# 5_SDRAM.net
KiCad netlist of a schematic drawn in Altium Designer
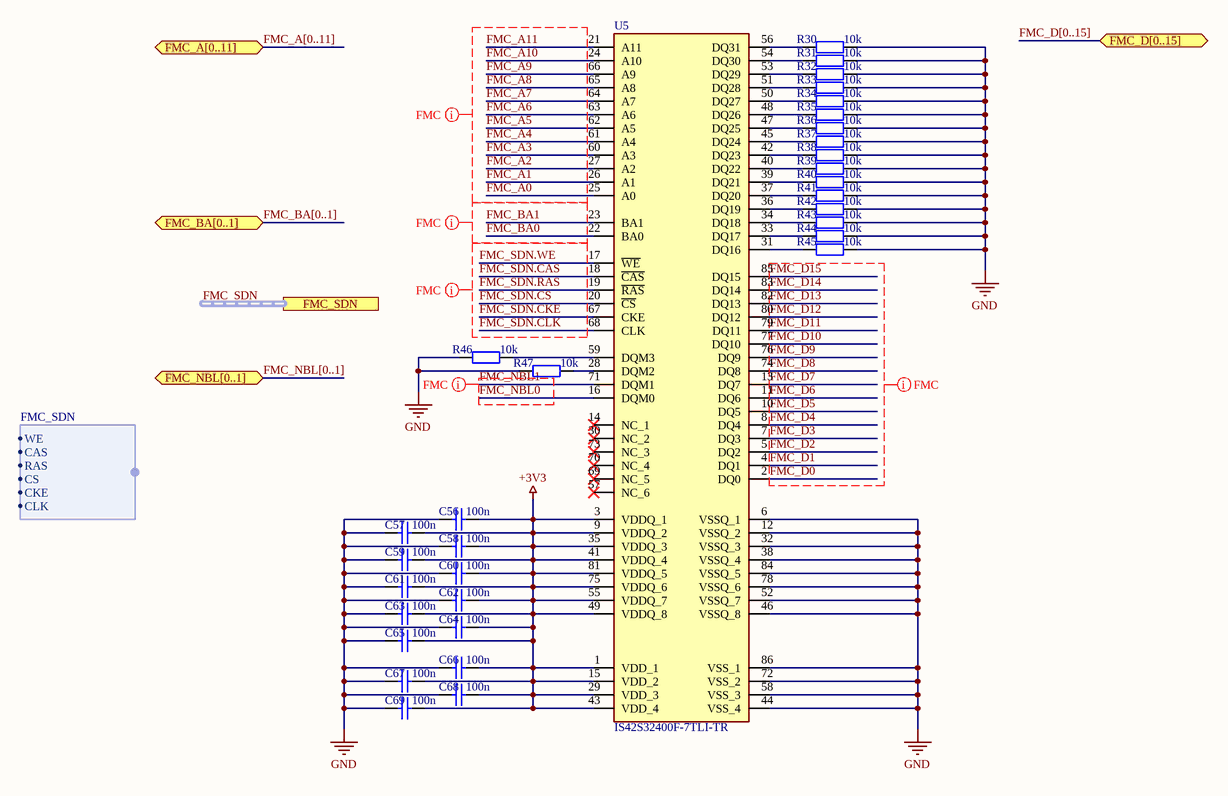
[diagram p0: [5] SDRAM.SchDoc]

(export (version "E")
  (design (tool "Eeschema 10.0.6"))
  (components
    (comp (ref "C56")
      (value "100n")
      (footprint "STguitar:Capacitor 0603")
      (description "Multilayer Ceramic Capacitors MLCC - SMD/SMT 0603 16VDC 0.1uF 10% X7R")
      (fields
        (field (name "MANUFACTURER PART NUMBER") "EMK107B7104KA-T")
        (field (name "MANUFACTURER") "Taiyo Yuden")
      )
      (libsource (lib "STguitar") (part "Capacitor 100n 10% 0603 EMK107B7104KA-T"))
    )
    (comp (ref "C57")
      (value "100n")
      (footprint "STguitar:Capacitor 0603")
      (description "Multilayer Ceramic Capacitors MLCC - SMD/SMT 0603 16VDC 0.1uF 10% X7R")
      (fields
        (field (name "MANUFACTURER PART NUMBER") "EMK107B7104KA-T")
        (field (name "MANUFACTURER") "Taiyo Yuden")
      )
      (libsource (lib "STguitar") (part "Capacitor 100n 10% 0603 EMK107B7104KA-T"))
    )
    (comp (ref "C58")
      (value "100n")
      (footprint "STguitar:Capacitor 0603")
      (description "Multilayer Ceramic Capacitors MLCC - SMD/SMT 0603 16VDC 0.1uF 10% X7R")
      (fields
        (field (name "MANUFACTURER PART NUMBER") "EMK107B7104KA-T")
        (field (name "MANUFACTURER") "Taiyo Yuden")
      )
      (libsource (lib "STguitar") (part "Capacitor 100n 10% 0603 EMK107B7104KA-T"))
    )
    (comp (ref "C59")
      (value "100n")
      (footprint "STguitar:Capacitor 0603")
      (description "Multilayer Ceramic Capacitors MLCC - SMD/SMT 0603 16VDC 0.1uF 10% X7R")
      (fields
        (field (name "MANUFACTURER PART NUMBER") "EMK107B7104KA-T")
        (field (name "MANUFACTURER") "Taiyo Yuden")
      )
      (libsource (lib "STguitar") (part "Capacitor 100n 10% 0603 EMK107B7104KA-T"))
    )
    (comp (ref "C60")
      (value "100n")
      (footprint "STguitar:Capacitor 0603")
      (description "Multilayer Ceramic Capacitors MLCC - SMD/SMT 0603 16VDC 0.1uF 10% X7R")
      (fields
        (field (name "MANUFACTURER PART NUMBER") "EMK107B7104KA-T")
        (field (name "MANUFACTURER") "Taiyo Yuden")
      )
      (libsource (lib "STguitar") (part "Capacitor 100n 10% 0603 EMK107B7104KA-T"))
    )
    (comp (ref "C61")
      (value "100n")
      (footprint "STguitar:Capacitor 0603")
      (description "Multilayer Ceramic Capacitors MLCC - SMD/SMT 0603 16VDC 0.1uF 10% X7R")
      (fields
        (field (name "MANUFACTURER PART NUMBER") "EMK107B7104KA-T")
        (field (name "MANUFACTURER") "Taiyo Yuden")
      )
      (libsource (lib "STguitar") (part "Capacitor 100n 10% 0603 EMK107B7104KA-T"))
    )
    (comp (ref "C62")
      (value "100n")
      (footprint "STguitar:Capacitor 0603")
      (description "Multilayer Ceramic Capacitors MLCC - SMD/SMT 0603 16VDC 0.1uF 10% X7R")
      (fields
        (field (name "MANUFACTURER PART NUMBER") "EMK107B7104KA-T")
        (field (name "MANUFACTURER") "Taiyo Yuden")
      )
      (libsource (lib "STguitar") (part "Capacitor 100n 10% 0603 EMK107B7104KA-T"))
    )
    (comp (ref "C63")
      (value "100n")
      (footprint "STguitar:Capacitor 0603")
      (description "Multilayer Ceramic Capacitors MLCC - SMD/SMT 0603 16VDC 0.1uF 10% X7R")
      (fields
        (field (name "MANUFACTURER PART NUMBER") "EMK107B7104KA-T")
        (field (name "MANUFACTURER") "Taiyo Yuden")
      )
      (libsource (lib "STguitar") (part "Capacitor 100n 10% 0603 EMK107B7104KA-T"))
    )
    (comp (ref "C64")
      (value "100n")
      (footprint "STguitar:Capacitor 0603")
      (description "Multilayer Ceramic Capacitors MLCC - SMD/SMT 0603 16VDC 0.1uF 10% X7R")
      (fields
        (field (name "MANUFACTURER PART NUMBER") "EMK107B7104KA-T")
        (field (name "MANUFACTURER") "Taiyo Yuden")
      )
      (libsource (lib "STguitar") (part "Capacitor 100n 10% 0603 EMK107B7104KA-T"))
    )
    (comp (ref "C65")
      (value "100n")
      (footprint "STguitar:Capacitor 0603")
      (description "Multilayer Ceramic Capacitors MLCC - SMD/SMT 0603 16VDC 0.1uF 10% X7R")
      (fields
        (field (name "MANUFACTURER PART NUMBER") "EMK107B7104KA-T")
        (field (name "MANUFACTURER") "Taiyo Yuden")
      )
      (libsource (lib "STguitar") (part "Capacitor 100n 10% 0603 EMK107B7104KA-T"))
    )
    (comp (ref "C66")
      (value "100n")
      (footprint "STguitar:Capacitor 0603")
      (description "Multilayer Ceramic Capacitors MLCC - SMD/SMT 0603 16VDC 0.1uF 10% X7R")
      (fields
        (field (name "MANUFACTURER PART NUMBER") "EMK107B7104KA-T")
        (field (name "MANUFACTURER") "Taiyo Yuden")
      )
      (libsource (lib "STguitar") (part "Capacitor 100n 10% 0603 EMK107B7104KA-T"))
    )
    (comp (ref "C67")
      (value "100n")
      (footprint "STguitar:Capacitor 0603")
      (description "Multilayer Ceramic Capacitors MLCC - SMD/SMT 0603 16VDC 0.1uF 10% X7R")
      (fields
        (field (name "MANUFACTURER PART NUMBER") "EMK107B7104KA-T")
        (field (name "MANUFACTURER") "Taiyo Yuden")
      )
      (libsource (lib "STguitar") (part "Capacitor 100n 10% 0603 EMK107B7104KA-T"))
    )
    (comp (ref "C68")
      (value "100n")
      (footprint "STguitar:Capacitor 0603")
      (description "Multilayer Ceramic Capacitors MLCC - SMD/SMT 0603 16VDC 0.1uF 10% X7R")
      (fields
        (field (name "MANUFACTURER PART NUMBER") "EMK107B7104KA-T")
        (field (name "MANUFACTURER") "Taiyo Yuden")
      )
      (libsource (lib "STguitar") (part "Capacitor 100n 10% 0603 EMK107B7104KA-T"))
    )
    (comp (ref "C69")
      (value "100n")
      (footprint "STguitar:Capacitor 0603")
      (description "Multilayer Ceramic Capacitors MLCC - SMD/SMT 0603 16VDC 0.1uF 10% X7R")
      (fields
        (field (name "MANUFACTURER PART NUMBER") "EMK107B7104KA-T")
        (field (name "MANUFACTURER") "Taiyo Yuden")
      )
      (libsource (lib "STguitar") (part "Capacitor 100n 10% 0603 EMK107B7104KA-T"))
    )
    (comp (ref "R30")
      (value "10k")
      (footprint "STguitar:Resistor 0603")
      (description "Thin Film Resistors - SMD 10K ohm 1% 1/10W")
      (fields
        (field (name "MANUFACTURER PART NUMBER") "RT0603FRE0710KL")
        (field (name "MANUFACTURER") "Yageo")
      )
      (libsource (lib "STguitar") (part "Resistor 10k 1% 0603 RT0603FRE0710KL"))
    )
    (comp (ref "R31")
      (value "10k")
      (footprint "STguitar:Resistor 0603")
      (description "Thin Film Resistors - SMD 10K ohm 1% 1/10W")
      (fields
        (field (name "MANUFACTURER PART NUMBER") "RT0603FRE0710KL")
        (field (name "MANUFACTURER") "Yageo")
      )
      (libsource (lib "STguitar") (part "Resistor 10k 1% 0603 RT0603FRE0710KL"))
    )
    (comp (ref "R32")
      (value "10k")
      (footprint "STguitar:Resistor 0603")
      (description "Thin Film Resistors - SMD 10K ohm 1% 1/10W")
      (fields
        (field (name "MANUFACTURER PART NUMBER") "RT0603FRE0710KL")
        (field (name "MANUFACTURER") "Yageo")
      )
      (libsource (lib "STguitar") (part "Resistor 10k 1% 0603 RT0603FRE0710KL"))
    )
    (comp (ref "R33")
      (value "10k")
      (footprint "STguitar:Resistor 0603")
      (description "Thin Film Resistors - SMD 10K ohm 1% 1/10W")
      (fields
        (field (name "MANUFACTURER PART NUMBER") "RT0603FRE0710KL")
        (field (name "MANUFACTURER") "Yageo")
      )
      (libsource (lib "STguitar") (part "Resistor 10k 1% 0603 RT0603FRE0710KL"))
    )
    (comp (ref "R34")
      (value "10k")
      (footprint "STguitar:Resistor 0603")
      (description "Thin Film Resistors - SMD 10K ohm 1% 1/10W")
      (fields
        (field (name "MANUFACTURER PART NUMBER") "RT0603FRE0710KL")
        (field (name "MANUFACTURER") "Yageo")
      )
      (libsource (lib "STguitar") (part "Resistor 10k 1% 0603 RT0603FRE0710KL"))
    )
    (comp (ref "R35")
      (value "10k")
      (footprint "STguitar:Resistor 0603")
      (description "Thin Film Resistors - SMD 10K ohm 1% 1/10W")
      (fields
        (field (name "MANUFACTURER PART NUMBER") "RT0603FRE0710KL")
        (field (name "MANUFACTURER") "Yageo")
      )
      (libsource (lib "STguitar") (part "Resistor 10k 1% 0603 RT0603FRE0710KL"))
    )
    (comp (ref "R36")
      (value "10k")
      (footprint "STguitar:Resistor 0603")
      (description "Thin Film Resistors - SMD 10K ohm 1% 1/10W")
      (fields
        (field (name "MANUFACTURER PART NUMBER") "RT0603FRE0710KL")
        (field (name "MANUFACTURER") "Yageo")
      )
      (libsource (lib "STguitar") (part "Resistor 10k 1% 0603 RT0603FRE0710KL"))
    )
    (comp (ref "R37")
      (value "10k")
      (footprint "STguitar:Resistor 0603")
      (description "Thin Film Resistors - SMD 10K ohm 1% 1/10W")
      (fields
        (field (name "MANUFACTURER PART NUMBER") "RT0603FRE0710KL")
        (field (name "MANUFACTURER") "Yageo")
      )
      (libsource (lib "STguitar") (part "Resistor 10k 1% 0603 RT0603FRE0710KL"))
    )
    (comp (ref "R38")
      (value "10k")
      (footprint "STguitar:Resistor 0603")
      (description "Thin Film Resistors - SMD 10K ohm 1% 1/10W")
      (fields
        (field (name "MANUFACTURER PART NUMBER") "RT0603FRE0710KL")
        (field (name "MANUFACTURER") "Yageo")
      )
      (libsource (lib "STguitar") (part "Resistor 10k 1% 0603 RT0603FRE0710KL"))
    )
    (comp (ref "R39")
      (value "10k")
      (footprint "STguitar:Resistor 0603")
      (description "Thin Film Resistors - SMD 10K ohm 1% 1/10W")
      (fields
        (field (name "MANUFACTURER PART NUMBER") "RT0603FRE0710KL")
        (field (name "MANUFACTURER") "Yageo")
      )
      (libsource (lib "STguitar") (part "Resistor 10k 1% 0603 RT0603FRE0710KL"))
    )
    (comp (ref "R40")
      (value "10k")
      (footprint "STguitar:Resistor 0603")
      (description "Thin Film Resistors - SMD 10K ohm 1% 1/10W")
      (fields
        (field (name "MANUFACTURER PART NUMBER") "RT0603FRE0710KL")
        (field (name "MANUFACTURER") "Yageo")
      )
      (libsource (lib "STguitar") (part "Resistor 10k 1% 0603 RT0603FRE0710KL"))
    )
    (comp (ref "R41")
      (value "10k")
      (footprint "STguitar:Resistor 0603")
      (description "Thin Film Resistors - SMD 10K ohm 1% 1/10W")
      (fields
        (field (name "MANUFACTURER PART NUMBER") "RT0603FRE0710KL")
        (field (name "MANUFACTURER") "Yageo")
      )
      (libsource (lib "STguitar") (part "Resistor 10k 1% 0603 RT0603FRE0710KL"))
    )
    (comp (ref "R42")
      (value "10k")
      (footprint "STguitar:Resistor 0603")
      (description "Thin Film Resistors - SMD 10K ohm 1% 1/10W")
      (fields
        (field (name "MANUFACTURER PART NUMBER") "RT0603FRE0710KL")
        (field (name "MANUFACTURER") "Yageo")
      )
      (libsource (lib "STguitar") (part "Resistor 10k 1% 0603 RT0603FRE0710KL"))
    )
    (comp (ref "R43")
      (value "10k")
      (footprint "STguitar:Resistor 0603")
      (description "Thin Film Resistors - SMD 10K ohm 1% 1/10W")
      (fields
        (field (name "MANUFACTURER PART NUMBER") "RT0603FRE0710KL")
        (field (name "MANUFACTURER") "Yageo")
      )
      (libsource (lib "STguitar") (part "Resistor 10k 1% 0603 RT0603FRE0710KL"))
    )
    (comp (ref "R44")
      (value "10k")
      (footprint "STguitar:Resistor 0603")
      (description "Thin Film Resistors - SMD 10K ohm 1% 1/10W")
      (fields
        (field (name "MANUFACTURER PART NUMBER") "RT0603FRE0710KL")
        (field (name "MANUFACTURER") "Yageo")
      )
      (libsource (lib "STguitar") (part "Resistor 10k 1% 0603 RT0603FRE0710KL"))
    )
    (comp (ref "R45")
      (value "10k")
      (footprint "STguitar:Resistor 0603")
      (description "Thin Film Resistors - SMD 10K ohm 1% 1/10W")
      (fields
        (field (name "MANUFACTURER PART NUMBER") "RT0603FRE0710KL")
        (field (name "MANUFACTURER") "Yageo")
      )
      (libsource (lib "STguitar") (part "Resistor 10k 1% 0603 RT0603FRE0710KL"))
    )
    (comp (ref "R46")
      (value "10k")
      (footprint "STguitar:Resistor 0603")
      (description "Thin Film Resistors - SMD 10K ohm 1% 1/10W")
      (fields
        (field (name "MANUFACTURER PART NUMBER") "RT0603FRE0710KL")
        (field (name "MANUFACTURER") "Yageo")
      )
      (libsource (lib "STguitar") (part "Resistor 10k 1% 0603 RT0603FRE0710KL"))
    )
    (comp (ref "R47")
      (value "10k")
      (footprint "STguitar:Resistor 0603")
      (description "Thin Film Resistors - SMD 10K ohm 1% 1/10W")
      (fields
        (field (name "MANUFACTURER PART NUMBER") "RT0603FRE0710KL")
        (field (name "MANUFACTURER") "Yageo")
      )
      (libsource (lib "STguitar") (part "Resistor 10k 1% 0603 RT0603FRE0710KL"))
    )
    (comp (ref "U5")
      (value "IS42S32400F-7TLI-TR")
      (footprint "STguitar:TSOP86")
      (description "DRAM 128M 4Mx32 143Mhz SDRAM, 3.3v")
      (fields (field (name "MANUFACTURER") "ISSI"))
      (libsource (lib "STguitar") (part "IC DRAM 128M 4Mx32 143Mhz SDRAM, 3.3V IS42S32400F-7TLI-TR"))
    )
  )
  (nets
    (net (code "2") (name "+3V3") (class "Default")
      (node (ref "C56") (pin "2") (pinfunction "2_2") (pintype "passive"))
      (node (ref "C57") (pin "2") (pinfunction "2_2") (pintype "passive"))
      (node (ref "C58") (pin "2") (pinfunction "2_2") (pintype "passive"))
      (node (ref "C59") (pin "2") (pinfunction "2_2") (pintype "passive"))
      (node (ref "C60") (pin "2") (pinfunction "2_2") (pintype "passive"))
      (node (ref "C61") (pin "2") (pinfunction "2_2") (pintype "passive"))
      (node (ref "C62") (pin "2") (pinfunction "2_2") (pintype "passive"))
      (node (ref "C63") (pin "2") (pinfunction "2_2") (pintype "passive"))
      (node (ref "C64") (pin "2") (pinfunction "2_2") (pintype "passive"))
      (node (ref "C65") (pin "2") (pinfunction "2_2") (pintype "passive"))
      (node (ref "C66") (pin "2") (pinfunction "2_2") (pintype "passive"))
      (node (ref "C67") (pin "2") (pinfunction "2_2") (pintype "passive"))
      (node (ref "C68") (pin "2") (pinfunction "2_2") (pintype "passive"))
      (node (ref "C69") (pin "2") (pinfunction "2_2") (pintype "passive"))
      (node (ref "U5") (pin "1") (pinfunction "VDD_1_1") (pintype "passive"))
      (node (ref "U5") (pin "15") (pinfunction "VDD_2_15") (pintype "passive"))
      (node (ref "U5") (pin "29") (pinfunction "VDD_3_29") (pintype "passive"))
      (node (ref "U5") (pin "3") (pinfunction "VDDQ_1_3") (pintype "passive"))
      (node (ref "U5") (pin "35") (pinfunction "VDDQ_3_35") (pintype "passive"))
      (node (ref "U5") (pin "41") (pinfunction "VDDQ_4_41") (pintype "passive"))
      (node (ref "U5") (pin "43") (pinfunction "VDD_4_43") (pintype "passive"))
      (node (ref "U5") (pin "49") (pinfunction "VDDQ_8_49") (pintype "passive"))
      (node (ref "U5") (pin "55") (pinfunction "VDDQ_7_55") (pintype "passive"))
      (node (ref "U5") (pin "75") (pinfunction "VDDQ_6_75") (pintype "passive"))
      (node (ref "U5") (pin "81") (pinfunction "VDDQ_5_81") (pintype "passive"))
      (node (ref "U5") (pin "9") (pinfunction "VDDQ_2_9") (pintype "passive"))
    )
    (net (code "3") (name "/FMC_A0") (class "Default")
      (node (ref "U5") (pin "25") (pinfunction "A0_25") (pintype "passive"))
    )
    (net (code "4") (name "/FMC_A1") (class "Default")
      (node (ref "U5") (pin "26") (pinfunction "A1_26") (pintype "passive"))
    )
    (net (code "5") (name "/FMC_A2") (class "Default")
      (node (ref "U5") (pin "27") (pinfunction "A2_27") (pintype "passive"))
    )
    (net (code "6") (name "/FMC_A3") (class "Default")
      (node (ref "U5") (pin "60") (pinfunction "A3_60") (pintype "passive"))
    )
    (net (code "7") (name "/FMC_A4") (class "Default")
      (node (ref "U5") (pin "61") (pinfunction "A4_61") (pintype "passive"))
    )
    (net (code "8") (name "/FMC_A5") (class "Default")
      (node (ref "U5") (pin "62") (pinfunction "A5_62") (pintype "passive"))
    )
    (net (code "9") (name "/FMC_A6") (class "Default")
      (node (ref "U5") (pin "63") (pinfunction "A6_63") (pintype "passive"))
    )
    (net (code "10") (name "/FMC_A7") (class "Default")
      (node (ref "U5") (pin "64") (pinfunction "A7_64") (pintype "passive"))
    )
    (net (code "11") (name "/FMC_A8") (class "Default")
      (node (ref "U5") (pin "65") (pinfunction "A8_65") (pintype "passive"))
    )
    (net (code "12") (name "/FMC_A9") (class "Default")
      (node (ref "U5") (pin "66") (pinfunction "A9_66") (pintype "passive"))
    )
    (net (code "13") (name "/FMC_A10") (class "Default")
      (node (ref "U5") (pin "24") (pinfunction "A10_24") (pintype "passive"))
    )
    (net (code "14") (name "/FMC_A11") (class "Default")
      (node (ref "U5") (pin "21") (pinfunction "A11_21") (pintype "passive"))
    )
    (net (code "16") (name "/FMC_BA0") (class "Default")
      (node (ref "U5") (pin "22") (pinfunction "BA0_22") (pintype "passive"))
    )
    (net (code "17") (name "/FMC_BA1") (class "Default")
      (node (ref "U5") (pin "23") (pinfunction "BA1_23") (pintype "passive"))
    )
    (net (code "19") (name "/FMC_D0") (class "Default")
      (node (ref "U5") (pin "2") (pinfunction "DQ0_2") (pintype "passive"))
    )
    (net (code "20") (name "/FMC_D1") (class "Default")
      (node (ref "U5") (pin "4") (pinfunction "DQ1_4") (pintype "passive"))
    )
    (net (code "21") (name "/FMC_D2") (class "Default")
      (node (ref "U5") (pin "5") (pinfunction "DQ2_5") (pintype "passive"))
    )
    (net (code "22") (name "/FMC_D3") (class "Default")
      (node (ref "U5") (pin "7") (pinfunction "DQ3_7") (pintype "passive"))
    )
    (net (code "23") (name "/FMC_D4") (class "Default")
      (node (ref "U5") (pin "8") (pinfunction "DQ4_8") (pintype "passive"))
    )
    (net (code "24") (name "/FMC_D5") (class "Default")
      (node (ref "U5") (pin "10") (pinfunction "DQ5_10") (pintype "passive"))
    )
    (net (code "25") (name "/FMC_D6") (class "Default")
      (node (ref "U5") (pin "11") (pinfunction "DQ6_11") (pintype "passive"))
    )
    (net (code "26") (name "/FMC_D7") (class "Default")
      (node (ref "U5") (pin "13") (pinfunction "DQ7_13") (pintype "passive"))
    )
    (net (code "27") (name "/FMC_D8") (class "Default")
      (node (ref "U5") (pin "74") (pinfunction "DQ8_74") (pintype "passive"))
    )
    (net (code "28") (name "/FMC_D9") (class "Default")
      (node (ref "U5") (pin "76") (pinfunction "DQ9_76") (pintype "passive"))
    )
    (net (code "29") (name "/FMC_D10") (class "Default")
      (node (ref "U5") (pin "77") (pinfunction "DQ10_77") (pintype "passive"))
    )
    (net (code "30") (name "/FMC_D11") (class "Default")
      (node (ref "U5") (pin "79") (pinfunction "DQ11_79") (pintype "passive"))
    )
    (net (code "31") (name "/FMC_D12") (class "Default")
      (node (ref "U5") (pin "80") (pinfunction "DQ12_80") (pintype "passive"))
    )
    (net (code "32") (name "/FMC_D13") (class "Default")
      (node (ref "U5") (pin "82") (pinfunction "DQ13_82") (pintype "passive"))
    )
    (net (code "33") (name "/FMC_D14") (class "Default")
      (node (ref "U5") (pin "83") (pinfunction "DQ14_83") (pintype "passive"))
    )
    (net (code "34") (name "/FMC_D15") (class "Default")
      (node (ref "U5") (pin "85") (pinfunction "DQ15_85") (pintype "passive"))
    )
    (net (code "36") (name "/FMC_NBL0") (class "Default")
      (node (ref "U5") (pin "16") (pinfunction "DQM0_16") (pintype "passive"))
    )
    (net (code "37") (name "/FMC_NBL1") (class "Default")
      (node (ref "U5") (pin "71") (pinfunction "DQM1_71") (pintype "passive"))
    )
    (net (code "39") (name "/FMC_SDN.CAS") (class "Default")
      (node (ref "U5") (pin "18") (pinfunction "~{CAS}_18") (pintype "passive"))
    )
    (net (code "40") (name "/FMC_SDN.CKE") (class "Default")
      (node (ref "U5") (pin "67") (pinfunction "CKE_67") (pintype "passive"))
    )
    (net (code "41") (name "/FMC_SDN.CLK") (class "Default")
      (node (ref "U5") (pin "68") (pinfunction "CLK_68") (pintype "passive"))
    )
    (net (code "42") (name "/FMC_SDN.CS") (class "Default")
      (node (ref "U5") (pin "20") (pinfunction "~{CS}_20") (pintype "passive"))
    )
    (net (code "43") (name "/FMC_SDN.RAS") (class "Default")
      (node (ref "U5") (pin "19") (pinfunction "~{RAS}_19") (pintype "passive"))
    )
    (net (code "44") (name "/FMC_SDN.WE") (class "Default")
      (node (ref "U5") (pin "17") (pinfunction "~{WE}_17") (pintype "passive"))
    )
    (net (code "46") (name "GND") (class "Default")
      (node (ref "C56") (pin "1") (pinfunction "1_1") (pintype "passive"))
      (node (ref "C57") (pin "1") (pinfunction "1_1") (pintype "passive"))
      (node (ref "C58") (pin "1") (pinfunction "1_1") (pintype "passive"))
      (node (ref "C59") (pin "1") (pinfunction "1_1") (pintype "passive"))
      (node (ref "C60") (pin "1") (pinfunction "1_1") (pintype "passive"))
      (node (ref "C61") (pin "1") (pinfunction "1_1") (pintype "passive"))
      (node (ref "C62") (pin "1") (pinfunction "1_1") (pintype "passive"))
      (node (ref "C63") (pin "1") (pinfunction "1_1") (pintype "passive"))
      (node (ref "C64") (pin "1") (pinfunction "1_1") (pintype "passive"))
      (node (ref "C65") (pin "1") (pinfunction "1_1") (pintype "passive"))
      (node (ref "C66") (pin "1") (pinfunction "1_1") (pintype "passive"))
      (node (ref "C67") (pin "1") (pinfunction "1_1") (pintype "passive"))
      (node (ref "C68") (pin "1") (pinfunction "1_1") (pintype "passive"))
      (node (ref "C69") (pin "1") (pinfunction "1_1") (pintype "passive"))
      (node (ref "R30") (pin "2") (pinfunction "2_2") (pintype "passive"))
      (node (ref "R31") (pin "2") (pinfunction "2_2") (pintype "passive"))
      (node (ref "R32") (pin "2") (pinfunction "2_2") (pintype "passive"))
      (node (ref "R33") (pin "2") (pinfunction "2_2") (pintype "passive"))
      (node (ref "R34") (pin "2") (pinfunction "2_2") (pintype "passive"))
      (node (ref "R35") (pin "2") (pinfunction "2_2") (pintype "passive"))
      (node (ref "R36") (pin "2") (pinfunction "2_2") (pintype "passive"))
      (node (ref "R37") (pin "2") (pinfunction "2_2") (pintype "passive"))
      (node (ref "R38") (pin "2") (pinfunction "2_2") (pintype "passive"))
      (node (ref "R39") (pin "2") (pinfunction "2_2") (pintype "passive"))
      (node (ref "R40") (pin "2") (pinfunction "2_2") (pintype "passive"))
      (node (ref "R41") (pin "2") (pinfunction "2_2") (pintype "passive"))
      (node (ref "R42") (pin "2") (pinfunction "2_2") (pintype "passive"))
      (node (ref "R43") (pin "2") (pinfunction "2_2") (pintype "passive"))
      (node (ref "R44") (pin "2") (pinfunction "2_2") (pintype "passive"))
      (node (ref "R45") (pin "2") (pinfunction "2_2") (pintype "passive"))
      (node (ref "R46") (pin "1") (pinfunction "1_1") (pintype "passive"))
      (node (ref "R47") (pin "1") (pinfunction "1_1") (pintype "passive"))
      (node (ref "U5") (pin "12") (pinfunction "VSSQ_2_12") (pintype "passive"))
      (node (ref "U5") (pin "32") (pinfunction "VSSQ_3_32") (pintype "passive"))
      (node (ref "U5") (pin "38") (pinfunction "VSSQ_4_38") (pintype "passive"))
      (node (ref "U5") (pin "44") (pinfunction "VSS_4_44") (pintype "passive"))
      (node (ref "U5") (pin "46") (pinfunction "VSSQ_8_46") (pintype "passive"))
      (node (ref "U5") (pin "52") (pinfunction "VSSQ_7_52") (pintype "passive"))
      (node (ref "U5") (pin "58") (pinfunction "VSS_3_58") (pintype "passive"))
      (node (ref "U5") (pin "6") (pinfunction "VSSQ_1_6") (pintype "passive"))
      (node (ref "U5") (pin "72") (pinfunction "VSS_2_72") (pintype "passive"))
      (node (ref "U5") (pin "78") (pinfunction "VSSQ_6_78") (pintype "passive"))
      (node (ref "U5") (pin "84") (pinfunction "VSSQ_5_84") (pintype "passive"))
      (node (ref "U5") (pin "86") (pinfunction "VSS_1_86") (pintype "passive"))
    )
    (net (code "47") (name "Net-(U5-DQ16)") (class "Default")
      (node (ref "R45") (pin "1") (pinfunction "1_1") (pintype "passive"))
      (node (ref "U5") (pin "31") (pinfunction "DQ16_31") (pintype "passive"))
    )
    (net (code "48") (name "Net-(U5-DQ17)") (class "Default")
      (node (ref "R44") (pin "1") (pinfunction "1_1") (pintype "passive"))
      (node (ref "U5") (pin "33") (pinfunction "DQ17_33") (pintype "passive"))
    )
    (net (code "49") (name "Net-(U5-DQ18)") (class "Default")
      (node (ref "R43") (pin "1") (pinfunction "1_1") (pintype "passive"))
      (node (ref "U5") (pin "34") (pinfunction "DQ18_34") (pintype "passive"))
    )
    (net (code "50") (name "Net-(U5-DQ19)") (class "Default")
      (node (ref "R42") (pin "1") (pinfunction "1_1") (pintype "passive"))
      (node (ref "U5") (pin "36") (pinfunction "DQ19_36") (pintype "passive"))
    )
    (net (code "51") (name "Net-(U5-DQ20)") (class "Default")
      (node (ref "R41") (pin "1") (pinfunction "1_1") (pintype "passive"))
      (node (ref "U5") (pin "37") (pinfunction "DQ20_37") (pintype "passive"))
    )
    (net (code "52") (name "Net-(U5-DQ21)") (class "Default")
      (node (ref "R40") (pin "1") (pinfunction "1_1") (pintype "passive"))
      (node (ref "U5") (pin "39") (pinfunction "DQ21_39") (pintype "passive"))
    )
    (net (code "53") (name "Net-(U5-DQ22)") (class "Default")
      (node (ref "R39") (pin "1") (pinfunction "1_1") (pintype "passive"))
      (node (ref "U5") (pin "40") (pinfunction "DQ22_40") (pintype "passive"))
    )
    (net (code "54") (name "Net-(U5-DQ23)") (class "Default")
      (node (ref "R38") (pin "1") (pinfunction "1_1") (pintype "passive"))
      (node (ref "U5") (pin "42") (pinfunction "DQ23_42") (pintype "passive"))
    )
    (net (code "55") (name "Net-(U5-DQ24)") (class "Default")
      (node (ref "R37") (pin "1") (pinfunction "1_1") (pintype "passive"))
      (node (ref "U5") (pin "45") (pinfunction "DQ24_45") (pintype "passive"))
    )
    (net (code "56") (name "Net-(U5-DQ25)") (class "Default")
      (node (ref "R36") (pin "1") (pinfunction "1_1") (pintype "passive"))
      (node (ref "U5") (pin "47") (pinfunction "DQ25_47") (pintype "passive"))
    )
    (net (code "57") (name "Net-(U5-DQ26)") (class "Default")
      (node (ref "R35") (pin "1") (pinfunction "1_1") (pintype "passive"))
      (node (ref "U5") (pin "48") (pinfunction "DQ26_48") (pintype "passive"))
    )
    (net (code "58") (name "Net-(U5-DQ27)") (class "Default")
      (node (ref "R34") (pin "1") (pinfunction "1_1") (pintype "passive"))
      (node (ref "U5") (pin "50") (pinfunction "DQ27_50") (pintype "passive"))
    )
    (net (code "59") (name "Net-(U5-DQ28)") (class "Default")
      (node (ref "R33") (pin "1") (pinfunction "1_1") (pintype "passive"))
      (node (ref "U5") (pin "51") (pinfunction "DQ28_51") (pintype "passive"))
    )
    (net (code "60") (name "Net-(U5-DQ29)") (class "Default")
      (node (ref "R32") (pin "1") (pinfunction "1_1") (pintype "passive"))
      (node (ref "U5") (pin "53") (pinfunction "DQ29_53") (pintype "passive"))
    )
    (net (code "61") (name "Net-(U5-DQ30)") (class "Default")
      (node (ref "R31") (pin "1") (pinfunction "1_1") (pintype "passive"))
      (node (ref "U5") (pin "54") (pinfunction "DQ30_54") (pintype "passive"))
    )
    (net (code "62") (name "Net-(U5-DQ31)") (class "Default")
      (node (ref "R30") (pin "1") (pinfunction "1_1") (pintype "passive"))
      (node (ref "U5") (pin "56") (pinfunction "DQ31_56") (pintype "passive"))
    )
    (net (code "63") (name "Net-(U5-DQM2)") (class "Default")
      (node (ref "R47") (pin "2") (pinfunction "2_2") (pintype "passive"))
      (node (ref "U5") (pin "28") (pinfunction "DQM2_28") (pintype "passive"))
    )
    (net (code "64") (name "Net-(U5-DQM3)") (class "Default")
      (node (ref "R46") (pin "2") (pinfunction "2_2") (pintype "passive"))
      (node (ref "U5") (pin "59") (pinfunction "DQM3_59") (pintype "passive"))
    )
    (net (code "65") (name "unconnected-(U5-NC_1-Pad14)") (class "Default")
      (node (ref "U5") (pin "14") (pinfunction "NC_1_14") (pintype "passive+no_connect"))
    )
    (net (code "66") (name "unconnected-(U5-NC_2-Pad30)") (class "Default")
      (node (ref "U5") (pin "30") (pinfunction "NC_2_30") (pintype "passive+no_connect"))
    )
    (net (code "67") (name "unconnected-(U5-NC_3-Pad73)") (class "Default")
      (node (ref "U5") (pin "73") (pinfunction "NC_3_73") (pintype "passive+no_connect"))
    )
    (net (code "68") (name "unconnected-(U5-NC_4-Pad70)") (class "Default")
      (node (ref "U5") (pin "70") (pinfunction "NC_4_70") (pintype "passive+no_connect"))
    )
    (net (code "69") (name "unconnected-(U5-NC_5-Pad69)") (class "Default")
      (node (ref "U5") (pin "69") (pinfunction "NC_5_69") (pintype "passive+no_connect"))
    )
    (net (code "70") (name "unconnected-(U5-NC_6-Pad57)") (class "Default")
      (node (ref "U5") (pin "57") (pinfunction "NC_6_57") (pintype "passive+no_connect"))
    )
  )
)
